# power_12V.net
KiCad netlist of a schematic drawn in Altium Designer
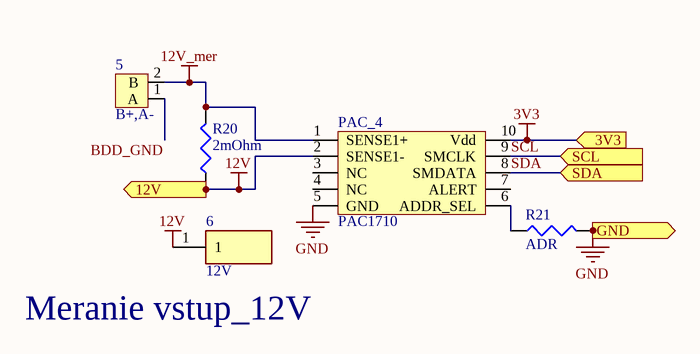
[diagram p0: power_12V.SchDoc]

(export (version "E")
  (design (tool "Eeschema 10.0.6"))
  (components
    (comp (ref "5")
      (value "B+,A-")
      (footprint "CON_2CH_PLUG")
      (description "TBG-5.0-KW-2P")
      (libsource (lib "SCH_Aquatec") (part "CON_2CH_PLUG"))
    )
    (comp (ref "6")
      (value "12V")
      (footprint "1508000150000030")
      (description "Undefined or Miscellaneous")
      (fields (field (name "MANUFACTURER_PART_NUMBER") "5015") (field (name "MOUSER PART NUMBER") "534-5015"))
      (libsource (lib "*") (part "5015"))
    )
    (comp (ref "PAC_4")
      (value "PAC1710")
      (footprint "PAC1710")
      (libsource (lib "SCH_Aquatec") (part "PAC1710"))
    )
    (comp (ref "R20")
      (value "2mOhm")
      (footprint "RESC3216X75N")
      (description "Resistor")
      (fields (field (name "PUBLISHER") "Altium Limited"))
      (libsource (lib "Miscellaneous Devices") (part "Res3"))
    )
    (comp (ref "R21")
      (value "ADR")
      (footprint "J1-0603")
      (description "Resistor")
      (fields (field (name "PUBLISHER") "Altium Limited"))
      (libsource (lib "Miscellaneous Devices") (part "Res3"))
    )
  )
  (nets
    (net (code "1") (name "/BDD_GND") (class "Default")
      (node (ref "5") (pin "1") (pinfunction "A_1") (pintype "passive"))
    )
    (net (code "2") (name "/SCL") (class "Default")
      (node (ref "PAC_4") (pin "9") (pinfunction "SMCLK_9") (pintype "passive"))
    )
    (net (code "3") (name "/SDA") (class "Default")
      (node (ref "PAC_4") (pin "8") (pinfunction "SMDATA_8") (pintype "passive"))
    )
    (net (code "4") (name "3V3") (class "Default")
      (node (ref "PAC_4") (pin "10") (pinfunction "Vdd_10") (pintype "passive"))
    )
    (net (code "5") (name "12V") (class "Default")
      (node (ref "6") (pin "1") (pinfunction "1_1") (pintype "passive"))
      (node (ref "PAC_4") (pin "2") (pinfunction "SENSE1-_2") (pintype "passive"))
      (node (ref "R20") (pin "1") (pinfunction "1_1") (pintype "passive"))
    )
    (net (code "6") (name "12V_mer") (class "Default")
      (node (ref "5") (pin "2") (pinfunction "B_2") (pintype "passive"))
      (node (ref "PAC_4") (pin "1") (pinfunction "SENSE1+_1") (pintype "passive"))
      (node (ref "R20") (pin "2") (pinfunction "2_2") (pintype "passive"))
    )
    (net (code "7") (name "GND") (class "Default")
      (node (ref "PAC_4") (pin "5") (pinfunction "GND_5") (pintype "passive"))
      (node (ref "R21") (pin "2") (pinfunction "2_2") (pintype "passive"))
    )
    (net (code "8") (name "Net-(PAC_4-ADDR_SEL)") (class "Default")
      (node (ref "PAC_4") (pin "6") (pinfunction "ADDR_SEL_6") (pintype "passive"))
      (node (ref "R21") (pin "1") (pinfunction "1_1") (pintype "passive"))
    )
    (net (code "9") (name "unconnected-(PAC_4-ALERT-Pad7)") (class "Default")
      (node (ref "PAC_4") (pin "7") (pinfunction "ALERT_7") (pintype "passive"))
    )
    (net (code "10") (name "unconnected-(PAC_4-NC-Pad3)") (class "Default")
      (node (ref "PAC_4") (pin "3") (pinfunction "NC_3") (pintype "passive"))
    )
    (net (code "11") (name "unconnected-(PAC_4-NC-Pad4)") (class "Default")
      (node (ref "PAC_4") (pin "4") (pinfunction "NC_4") (pintype "passive"))
    )
  )
)
